# GSM_Modem_Antenna.net
KiCad netlist of a schematic drawn in Altium Designer
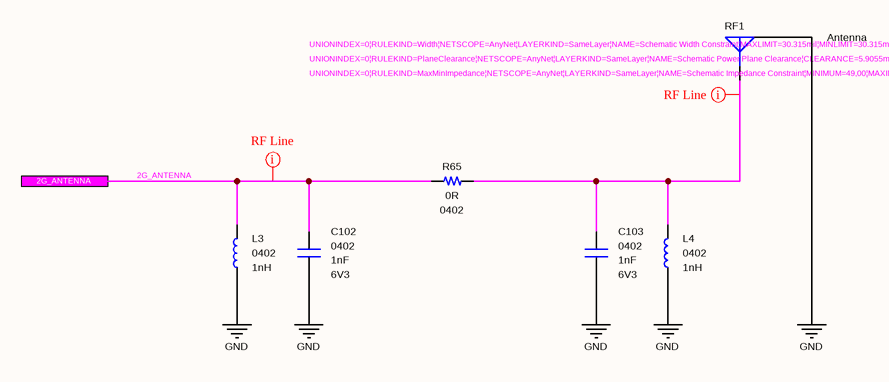
[diagram p0: GSM Modem Antenna.SchDoc]

(export (version "E")
  (design (tool "Eeschema 10.0.6"))
  (components
    (comp (ref "C102")
      (value "1nF")
      (footprint "CAPACITOR_0402")
      (description "Capacitor - 1nF [0402] (Ceramic)")
      (fields
        (field (name "TOLERANCE") "20%")
        (field (name "CASE") "0402")
        (field (name "VOLTAGE") "6V3")
        (field (name "MANUFACTURER PART NUMBER") "04026C102MAT2A")
      )
      (libsource (lib "Ovoo_Library") (part "Capacitor - 1nF [0402-6V3]"))
    )
    (comp (ref "C103")
      (value "1nF")
      (footprint "CAPACITOR_0402")
      (description "Capacitor - 1nF [0402] (Ceramic)")
      (fields
        (field (name "TOLERANCE") "20%")
        (field (name "CASE") "0402")
        (field (name "VOLTAGE") "6V3")
        (field (name "MANUFACTURER PART NUMBER") "04026C102MAT2A")
      )
      (libsource (lib "Ovoo_Library") (part "Capacitor - 1nF [0402-6V3]"))
    )
    (comp (ref "L3")
      (value "1nH")
      (footprint "INDUCTOR_0402")
      (description "Fixed Inductor")
      (fields
        (field (name "TOLERANCE") "0.3 nH")
        (field (name "CASE") "0402")
        (field (name "MANUFACTURER PART NUMBER") "LQG15HN1N0S02D")
      )
      (libsource (lib "Ovoo_Library") (part "Inductor - 1nH [0402]"))
    )
    (comp (ref "L4")
      (value "1nH")
      (footprint "INDUCTOR_0402")
      (description "Fixed Inductor")
      (fields
        (field (name "TOLERANCE") "0.3 nH")
        (field (name "CASE") "0402")
        (field (name "MANUFACTURER PART NUMBER") "LQG15HN1N0S02D")
      )
      (libsource (lib "Ovoo_Library") (part "Inductor - 1nH [0402]"))
    )
    (comp (ref "R65")
      (value "0R")
      (footprint "RESISTOR_0402")
      (description "Thick Film Resistors - SMD 1/16 W 0 Ohms")
      (fields
        (field (name "CASE") "0402")
        (field (name "MANUFACTURER PART NUMBER") "CRCW04020000Z0ED")
        (field (name "MOUSER PART NUMBER") "71-CRCW0402-0-E3")
      )
      (libsource (lib "Ovoo_Library") (part "Resistor - 0R"))
    )
    (comp (ref "RF1")
      (value "Antenna")
      (footprint "Connector_IPEX")
      (description "MHF Antenna Socket")
      (libsource (lib "Ovoo_Library") (part "Connector - MHF"))
    )
  )
  (nets
    (net (code "1") (name "/2G_ANTENNA") (class "Default")
      (node (ref "C102") (pin "2") (pinfunction "2_2") (pintype "passive"))
      (node (ref "L3") (pin "2") (pinfunction "2_2") (pintype "passive"))
      (node (ref "R65") (pin "2") (pinfunction "2_2") (pintype "passive"))
    )
    (net (code "2") (name "GND") (class "Default")
      (node (ref "C102") (pin "1") (pinfunction "1_1") (pintype "passive"))
      (node (ref "C103") (pin "1") (pinfunction "1_1") (pintype "passive"))
      (node (ref "L3") (pin "1") (pinfunction "1_1") (pintype "passive"))
      (node (ref "L4") (pin "1") (pinfunction "1_1") (pintype "passive"))
      (node (ref "RF1") (pin "2") (pinfunction "GND_2") (pintype "passive"))
    )
    (net (code "3") (name "Net-(RF1-Signal)") (class "Default")
      (node (ref "C103") (pin "2") (pinfunction "2_2") (pintype "passive"))
      (node (ref "L4") (pin "2") (pinfunction "2_2") (pintype "passive"))
      (node (ref "R65") (pin "1") (pinfunction "1_1") (pintype "passive"))
      (node (ref "RF1") (pin "1") (pinfunction "Signal_1") (pintype "passive"))
    )
  )
)
